# -V1_0.net
KiCad netlist of a schematic drawn in Altium Designer
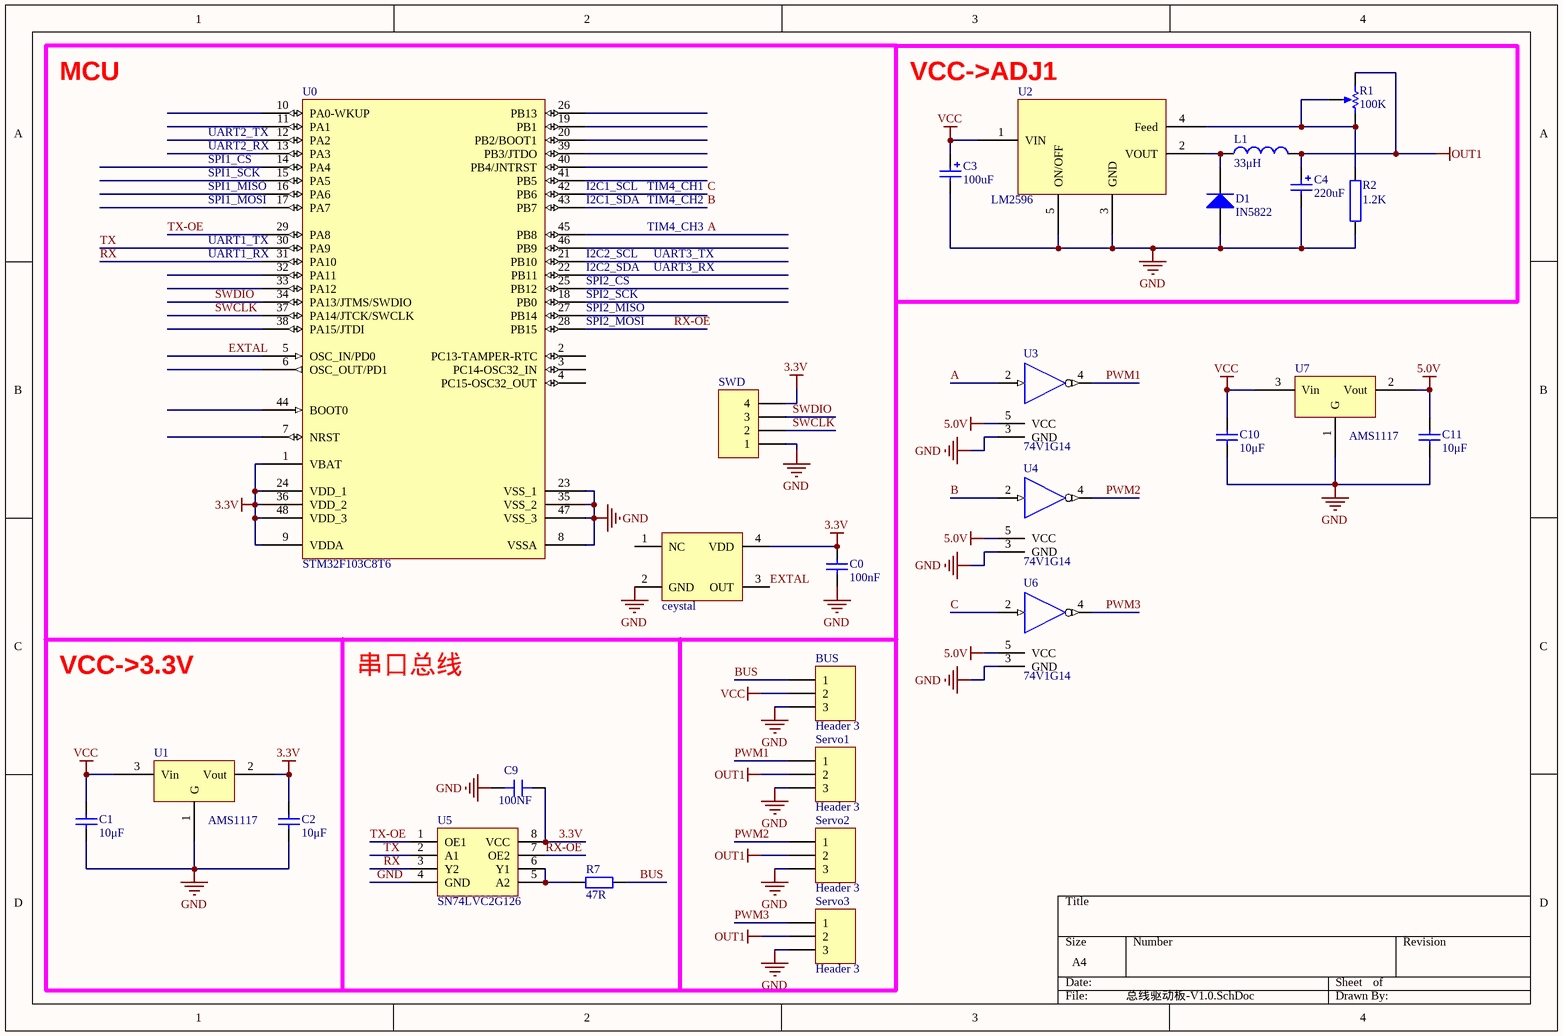
[diagram p0: 总线驱动板-V1.0.SchDoc]

(export (version "E")
  (design (tool "Eeschema 10.0.6"))
  (components
    (comp (ref "BUS")
      (value "Header 3")
      (footprint "3P")
      (description "Header, 3-Pin")
      (fields (field (name "PUBLISHER") "Altium Limited"))
      (libsource (lib "12th_MAINBOARD_3D") (part "Header 3"))
    )
    (comp (ref "C0")
      (value "100nF")
      (footprint "C0603")
      (description "Capacitor (Semiconductor SIM Model)")
      (fields (field (name "Comment") "C0603") (field (name "PUBLISHER") "Altium Limited"))
      (libsource (lib "K66") (part "Cap(0603)"))
    )
    (comp (ref "C1")
      (value "10μF")
      (footprint "Cap_0603")
      (fields (field (name "Comment") "C0603"))
      (libsource (lib "E_Library") (part "Cap0603"))
    )
    (comp (ref "C2")
      (value "10μF")
      (footprint "Cap_0603")
      (fields (field (name "Comment") "C0603"))
      (libsource (lib "E_Library") (part "Cap0603"))
    )
    (comp (ref "C3")
      (value "100uF")
      (footprint "Cap_electrolitic_φ3.5_8")
      (description "Polarized Capacitor (Radial)")
      (fields (field (name "Comment") "CAP_B") (field (name "PUBLISHER") "Altium Limited"))
      (libsource (lib "DR-WiFi Servo") (part "CAP_B"))
    )
    (comp (ref "C4")
      (value "220uF")
      (footprint "Cap_electrolitic_φ3.5_8")
      (description "Polarized Capacitor (Radial)")
      (fields (field (name "Comment") "CAP_B") (field (name "PUBLISHER") "Altium Limited"))
      (libsource (lib "DR-WiFi Servo") (part "CAP_B"))
    )
    (comp (ref "C9")
      (value "100NF")
      (footprint "Cap_0603")
      (fields (field (name "Comment") "C0603"))
      (libsource (lib "常用") (part "Cap 1"))
    )
    (comp (ref "C10")
      (value "10μF")
      (footprint "Cap_0603")
      (fields (field (name "Comment") "C0603"))
      (libsource (lib "E_Library") (part "Cap0603"))
    )
    (comp (ref "C11")
      (value "10μF")
      (footprint "Cap_0603")
      (fields (field (name "Comment") "C0603"))
      (libsource (lib "E_Library") (part "Cap0603"))
    )
    (comp (ref "ceystal")
      (value "32MHz")
      (footprint "crystal")
      (libsource (lib "K66") (part "CRYSTAL OSCILLATOR"))
    )
    (comp (ref "D1") (value "IN5822") (footprint "0805D") (libsource (lib "E_Library") (part "Diode")))
    (comp (ref "L1")
      (value "33μH")
      (footprint "INDUCTOR")
      (fields (field (name "Comment") "INDUCTOR"))
      (libsource (lib "E_Library") (part "INDUCTOR"))
    )
    (comp (ref "R1")
      (value "100K")
      (footprint "SIP-3")
      (description "Potentiometer")
      (fields (field (name "Comment") "RPot") (field (name "PUBLISHER") "Altium Limited"))
      (libsource (lib "Miscellaneous Devices") (part "RPot"))
    )
    (comp (ref "R2")
      (value "1.2K")
      (footprint "Res_0603")
      (description "Resistor")
      (fields (field (name "Comment") "R0603"))
      (libsource (lib "DR-WiFi Servo") (part "RES"))
    )
    (comp (ref "R7")
      (value "47R")
      (footprint "Res_0603")
      (fields (field (name "Comment") "R0603"))
      (libsource (lib "常用") (part "Res2"))
    )
    (comp (ref "Servo1")
      (value "Header 3")
      (footprint "3P")
      (description "Header, 3-Pin")
      (fields (field (name "PUBLISHER") "Altium Limited"))
      (libsource (lib "12th_MAINBOARD_3D") (part "Header 3"))
    )
    (comp (ref "Servo2")
      (value "Header 3")
      (footprint "3P")
      (description "Header, 3-Pin")
      (fields (field (name "PUBLISHER") "Altium Limited"))
      (libsource (lib "12th_MAINBOARD_3D") (part "Header 3"))
    )
    (comp (ref "Servo3")
      (value "Header 3")
      (footprint "3P")
      (description "Header, 3-Pin")
      (fields (field (name "PUBLISHER") "Altium Limited"))
      (libsource (lib "12th_MAINBOARD_3D") (part "Header 3"))
    )
    (comp (ref "SWD")
      (value "Header 4")
      (footprint "HDR1X4_")
      (description "Header, 4-Pin")
      (fields (field (name "PUBLISHER") "Altium Limited"))
      (libsource (lib "Mainboard_for_GraPro_of_Leo_1") (part "Header 4"))
    )
    (comp (ref "U0")
      (value "STM32F103C8T6")
      (footprint "LC-LQFP-48_7x7x05P")
      (description "STM32 ARM-based 32-bit MCU with 64 Kbytes Flash, 48-pin LQFP, Industrial Temperature")
      (fields (field (name "PUBLISHER") "Altium Limited"))
      (libsource (lib "PCB_Project1") (part "STM32F103C8T6"))
    )
    (comp (ref "U1")
      (value "AMS1117")
      (footprint "LC-SOT-89(SOT-89-3)")
      (libsource (lib "my_library") (part "AMS1117"))
    )
    (comp (ref "U2") (value "LM2596") (footprint "LC-TO-263-5") (libsource (lib "电源") (part "LM2596")))
    (comp (ref "U3") (value "74V1G14") (footprint "SOT-23-5") (libsource (lib "E_Library") (part "74V1G14")))
    (comp (ref "U4") (value "74V1G14") (footprint "SOT-23-5") (libsource (lib "E_Library") (part "74V1G14")))
    (comp (ref "U5")
      (value "SN74LVC2G126")
      (footprint "VSSOP-8")
      (libsource (lib "运放逻辑") (part "SN74LVC2G126"))
    )
    (comp (ref "U6") (value "74V1G14") (footprint "SOT-23-5") (libsource (lib "E_Library") (part "74V1G14")))
    (comp (ref "U7")
      (value "AMS1117")
      (footprint "LC-SOT-89(SOT-89-3)")
      (libsource (lib "my_library") (part "AMS1117"))
    )
  )
  (nets
    (net (code "1") (name "/A") (class "Default")
      (node (ref "U0") (pin "45") (pinfunction "PB8_45") (pintype "bidirectional"))
      (node (ref "U3") (pin "2") (pinfunction "A_2") (pintype "input"))
    )
    (net (code "2") (name "/B") (class "Default")
      (node (ref "U0") (pin "43") (pinfunction "PB7_43") (pintype "bidirectional"))
      (node (ref "U4") (pin "2") (pinfunction "A_2") (pintype "input"))
    )
    (net (code "3") (name "/BUS") (class "Default")
      (node (ref "BUS") (pin "1") (pinfunction "1_1") (pintype "passive"))
      (node (ref "R7") (pin "1") (pinfunction "1_1") (pintype "passive"))
    )
    (net (code "4") (name "/C") (class "Default")
      (node (ref "U0") (pin "42") (pinfunction "PB6_42") (pintype "bidirectional"))
      (node (ref "U6") (pin "2") (pinfunction "A_2") (pintype "input"))
    )
    (net (code "5") (name "/EXTAL") (class "Default")
      (node (ref "U0") (pin "5") (pinfunction "OSC_IN/PD0_5") (pintype "input"))
      (node (ref "ceystal") (pin "3") (pinfunction "OUT_3") (pintype "passive"))
    )
    (net (code "6") (name "/PWM1") (class "Default")
      (node (ref "Servo1") (pin "1") (pinfunction "1_1") (pintype "passive"))
      (node (ref "U3") (pin "4") (pinfunction "Y_4") (pintype "output"))
    )
    (net (code "7") (name "/PWM2") (class "Default")
      (node (ref "Servo2") (pin "1") (pinfunction "1_1") (pintype "passive"))
      (node (ref "U4") (pin "4") (pinfunction "Y_4") (pintype "output"))
    )
    (net (code "8") (name "/PWM3") (class "Default")
      (node (ref "Servo3") (pin "1") (pinfunction "1_1") (pintype "passive"))
      (node (ref "U6") (pin "4") (pinfunction "Y_4") (pintype "output"))
    )
    (net (code "9") (name "/RX") (class "Default")
      (node (ref "U0") (pin "31") (pinfunction "PA10_31") (pintype "bidirectional"))
      (node (ref "U5") (pin "3") (pinfunction "Y2_3") (pintype "passive"))
    )
    (net (code "10") (name "/RX-OE") (class "Default")
      (node (ref "U0") (pin "28") (pinfunction "PB15_28") (pintype "bidirectional"))
      (node (ref "U5") (pin "7") (pinfunction "OE2_7") (pintype "passive"))
    )
    (net (code "11") (name "/SWCLK") (class "Default")
      (node (ref "SWD") (pin "2") (pinfunction "2_2") (pintype "passive"))
      (node (ref "U0") (pin "37") (pinfunction "PA14/JTCK/SWCLK_37") (pintype "bidirectional"))
    )
    (net (code "12") (name "/SWDIO") (class "Default")
      (node (ref "SWD") (pin "3") (pinfunction "3_3") (pintype "passive"))
      (node (ref "U0") (pin "34") (pinfunction "PA13/JTMS/SWDIO_34") (pintype "bidirectional"))
    )
    (net (code "13") (name "/TX") (class "Default")
      (node (ref "U0") (pin "30") (pinfunction "PA9_30") (pintype "bidirectional"))
      (node (ref "U5") (pin "2") (pinfunction "A1_2") (pintype "passive"))
    )
    (net (code "14") (name "/TX-OE") (class "Default")
      (node (ref "U0") (pin "29") (pinfunction "PA8_29") (pintype "bidirectional"))
      (node (ref "U5") (pin "1") (pinfunction "OE1_1") (pintype "passive"))
    )
    (net (code "15") (name "3.3V") (class "Default")
      (node (ref "C0") (pin "2") (pinfunction "2_2") (pintype "passive"))
      (node (ref "C2") (pin "2") (pinfunction "2_2") (pintype "passive"))
      (node (ref "C9") (pin "1") (pinfunction "1_1") (pintype "passive"))
      (node (ref "SWD") (pin "4") (pinfunction "4_4") (pintype "passive"))
      (node (ref "U0") (pin "1") (pinfunction "VBAT_1") (pintype "power_in"))
      (node (ref "U0") (pin "24") (pinfunction "VDD_1_24") (pintype "power_in"))
      (node (ref "U0") (pin "36") (pinfunction "VDD_2_36") (pintype "power_in"))
      (node (ref "U0") (pin "48") (pinfunction "VDD_3_48") (pintype "power_in"))
      (node (ref "U0") (pin "9") (pinfunction "VDDA_9") (pintype "power_in"))
      (node (ref "U1") (pin "2") (pinfunction "Vout_2") (pintype "passive"))
      (node (ref "U5") (pin "8") (pinfunction "VCC_8") (pintype "passive"))
      (node (ref "ceystal") (pin "4") (pinfunction "VDD_4") (pintype "passive"))
    )
    (net (code "16") (name "5.0V") (class "Default")
      (node (ref "C11") (pin "2") (pinfunction "2_2") (pintype "passive"))
      (node (ref "U3") (pin "5") (pinfunction "VCC_5") (pintype "power_in"))
      (node (ref "U4") (pin "5") (pinfunction "VCC_5") (pintype "power_in"))
      (node (ref "U6") (pin "5") (pinfunction "VCC_5") (pintype "power_in"))
      (node (ref "U7") (pin "2") (pinfunction "Vout_2") (pintype "passive"))
    )
    (net (code "17") (name "GND") (class "Default")
      (node (ref "BUS") (pin "3") (pinfunction "3_3") (pintype "passive"))
      (node (ref "C0") (pin "1") (pinfunction "1_1") (pintype "passive"))
      (node (ref "C1") (pin "1") (pinfunction "1_1") (pintype "passive"))
      (node (ref "C10") (pin "1") (pinfunction "1_1") (pintype "passive"))
      (node (ref "C11") (pin "1") (pinfunction "1_1") (pintype "passive"))
      (node (ref "C2") (pin "1") (pinfunction "1_1") (pintype "passive"))
      (node (ref "C3") (pin "2") (pinfunction "2_2") (pintype "passive"))
      (node (ref "C4") (pin "2") (pinfunction "2_2") (pintype "passive"))
      (node (ref "C9") (pin "2") (pinfunction "2_2") (pintype "passive"))
      (node (ref "D1") (pin "A") (pinfunction "A_A") (pintype "passive"))
      (node (ref "R2") (pin "2") (pinfunction "BOT_2") (pintype "passive"))
      (node (ref "SWD") (pin "1") (pinfunction "1_1") (pintype "passive"))
      (node (ref "Servo1") (pin "3") (pinfunction "3_3") (pintype "passive"))
      (node (ref "Servo2") (pin "3") (pinfunction "3_3") (pintype "passive"))
      (node (ref "Servo3") (pin "3") (pinfunction "3_3") (pintype "passive"))
      (node (ref "U0") (pin "23") (pinfunction "VSS_1_23") (pintype "power_in"))
      (node (ref "U0") (pin "35") (pinfunction "VSS_2_35") (pintype "power_in"))
      (node (ref "U0") (pin "47") (pinfunction "VSS_3_47") (pintype "power_in"))
      (node (ref "U0") (pin "8") (pinfunction "VSSA_8") (pintype "power_in"))
      (node (ref "U1") (pin "1") (pinfunction "G_1") (pintype "passive"))
      (node (ref "U2") (pin "3") (pinfunction "GND_3") (pintype "passive"))
      (node (ref "U2") (pin "5") (pinfunction "ON/OFF_5") (pintype "passive"))
      (node (ref "U3") (pin "3") (pinfunction "GND_3") (pintype "power_in"))
      (node (ref "U4") (pin "3") (pinfunction "GND_3") (pintype "power_in"))
      (node (ref "U5") (pin "4") (pinfunction "GND_4") (pintype "passive"))
      (node (ref "U6") (pin "3") (pinfunction "GND_3") (pintype "power_in"))
      (node (ref "U7") (pin "1") (pinfunction "G_1") (pintype "passive"))
      (node (ref "ceystal") (pin "2") (pinfunction "GND_2") (pintype "passive"))
    )
    (net (code "18") (name "Net-(R1-BOT)") (class "Default")
      (node (ref "R1") (pin "2") (pinfunction "BOT_2") (pintype "passive"))
      (node (ref "R1") (pin "3") (pinfunction "TAP_3") (pintype "passive"))
      (node (ref "R2") (pin "1") (pinfunction "TOP_1") (pintype "passive"))
      (node (ref "U2") (pin "4") (pinfunction "Feed_4") (pintype "passive"))
    )
    (net (code "19") (name "Net-(U2-VOUT)") (class "Default")
      (node (ref "D1") (pin "K") (pinfunction "K_K") (pintype "passive"))
      (node (ref "L1") (pin "1") (pinfunction "1_1") (pintype "passive"))
      (node (ref "U2") (pin "2") (pinfunction "VOUT_2") (pintype "passive"))
    )
    (net (code "20") (name "Net-(U5-A2)") (class "Default")
      (node (ref "R7") (pin "2") (pinfunction "2_2") (pintype "passive"))
      (node (ref "U5") (pin "5") (pinfunction "A2_5") (pintype "passive"))
      (node (ref "U5") (pin "6") (pinfunction "Y1_6") (pintype "passive"))
    )
    (net (code "21") (name "OUT1") (class "Default")
      (node (ref "C4") (pin "1") (pinfunction "1_1") (pintype "passive"))
      (node (ref "L1") (pin "2") (pinfunction "2_2") (pintype "passive"))
      (node (ref "R1") (pin "1") (pinfunction "TOP_1") (pintype "passive"))
      (node (ref "Servo1") (pin "2") (pinfunction "2_2") (pintype "passive"))
      (node (ref "Servo2") (pin "2") (pinfunction "2_2") (pintype "passive"))
      (node (ref "Servo3") (pin "2") (pinfunction "2_2") (pintype "passive"))
    )
    (net (code "22") (name "VCC") (class "Default")
      (node (ref "BUS") (pin "2") (pinfunction "2_2") (pintype "passive"))
      (node (ref "C1") (pin "2") (pinfunction "2_2") (pintype "passive"))
      (node (ref "C10") (pin "2") (pinfunction "2_2") (pintype "passive"))
      (node (ref "C3") (pin "1") (pinfunction "1_1") (pintype "passive"))
      (node (ref "U1") (pin "3") (pinfunction "Vin_3") (pintype "passive"))
      (node (ref "U2") (pin "1") (pinfunction "VIN_1") (pintype "passive"))
      (node (ref "U7") (pin "3") (pinfunction "Vin_3") (pintype "passive"))
    )
    (net (code "23") (name "unconnected-(U0-BOOT0-Pad44)") (class "Default")
      (node (ref "U0") (pin "44") (pinfunction "BOOT0_44") (pintype "input"))
    )
    (net (code "24") (name "unconnected-(U0-NRST-Pad7)") (class "Default")
      (node (ref "U0") (pin "7") (pinfunction "NRST_7") (pintype "bidirectional"))
    )
    (net (code "25") (name "unconnected-(U0-OSC_OUT{slash}PD1-Pad6)") (class "Default")
      (node (ref "U0") (pin "6") (pinfunction "OSC_OUT/PD1_6") (pintype "output"))
    )
    (net (code "26") (name "unconnected-(U0-PA0-WKUP-Pad10)") (class "Default")
      (node (ref "U0") (pin "10") (pinfunction "PA0-WKUP_10") (pintype "bidirectional"))
    )
    (net (code "27") (name "unconnected-(U0-PA1-Pad11)") (class "Default")
      (node (ref "U0") (pin "11") (pinfunction "PA1_11") (pintype "bidirectional"))
    )
    (net (code "28") (name "unconnected-(U0-PA2-Pad12)") (class "Default")
      (node (ref "U0") (pin "12") (pinfunction "PA2_12") (pintype "bidirectional"))
    )
    (net (code "29") (name "unconnected-(U0-PA3-Pad13)") (class "Default")
      (node (ref "U0") (pin "13") (pinfunction "PA3_13") (pintype "bidirectional"))
    )
    (net (code "30") (name "unconnected-(U0-PA4-Pad14)") (class "Default")
      (node (ref "U0") (pin "14") (pinfunction "PA4_14") (pintype "bidirectional"))
    )
    (net (code "31") (name "unconnected-(U0-PA5-Pad15)") (class "Default")
      (node (ref "U0") (pin "15") (pinfunction "PA5_15") (pintype "bidirectional"))
    )
    (net (code "32") (name "unconnected-(U0-PA6-Pad16)") (class "Default")
      (node (ref "U0") (pin "16") (pinfunction "PA6_16") (pintype "bidirectional"))
    )
    (net (code "33") (name "unconnected-(U0-PA7-Pad17)") (class "Default")
      (node (ref "U0") (pin "17") (pinfunction "PA7_17") (pintype "bidirectional"))
    )
    (net (code "34") (name "unconnected-(U0-PA11-Pad32)") (class "Default")
      (node (ref "U0") (pin "32") (pinfunction "PA11_32") (pintype "bidirectional"))
    )
    (net (code "35") (name "unconnected-(U0-PA12-Pad33)") (class "Default")
      (node (ref "U0") (pin "33") (pinfunction "PA12_33") (pintype "bidirectional"))
    )
    (net (code "36") (name "unconnected-(U0-PA15{slash}JTDI-Pad38)") (class "Default")
      (node (ref "U0") (pin "38") (pinfunction "PA15/JTDI_38") (pintype "bidirectional"))
    )
    (net (code "37") (name "unconnected-(U0-PB0-Pad18)") (class "Default")
      (node (ref "U0") (pin "18") (pinfunction "PB0_18") (pintype "bidirectional"))
    )
    (net (code "38") (name "unconnected-(U0-PB1-Pad19)") (class "Default")
      (node (ref "U0") (pin "19") (pinfunction "PB1_19") (pintype "bidirectional"))
    )
    (net (code "39") (name "unconnected-(U0-PB2{slash}BOOT1-Pad20)") (class "Default")
      (node (ref "U0") (pin "20") (pinfunction "PB2/BOOT1_20") (pintype "bidirectional"))
    )
    (net (code "40") (name "unconnected-(U0-PB3{slash}JTDO-Pad39)") (class "Default")
      (node (ref "U0") (pin "39") (pinfunction "PB3/JTDO_39") (pintype "bidirectional"))
    )
    (net (code "41") (name "unconnected-(U0-PB4{slash}JNTRST-Pad40)") (class "Default")
      (node (ref "U0") (pin "40") (pinfunction "PB4/JNTRST_40") (pintype "bidirectional"))
    )
    (net (code "42") (name "unconnected-(U0-PB5-Pad41)") (class "Default")
      (node (ref "U0") (pin "41") (pinfunction "PB5_41") (pintype "bidirectional"))
    )
    (net (code "43") (name "unconnected-(U0-PB9-Pad46)") (class "Default")
      (node (ref "U0") (pin "46") (pinfunction "PB9_46") (pintype "bidirectional"))
    )
    (net (code "44") (name "unconnected-(U0-PB10-Pad21)") (class "Default")
      (node (ref "U0") (pin "21") (pinfunction "PB10_21") (pintype "bidirectional"))
    )
    (net (code "45") (name "unconnected-(U0-PB11-Pad22)") (class "Default")
      (node (ref "U0") (pin "22") (pinfunction "PB11_22") (pintype "bidirectional"))
    )
    (net (code "46") (name "unconnected-(U0-PB12-Pad25)") (class "Default")
      (node (ref "U0") (pin "25") (pinfunction "PB12_25") (pintype "bidirectional"))
    )
    (net (code "47") (name "unconnected-(U0-PB13-Pad26)") (class "Default")
      (node (ref "U0") (pin "26") (pinfunction "PB13_26") (pintype "bidirectional"))
    )
    (net (code "48") (name "unconnected-(U0-PB14-Pad27)") (class "Default")
      (node (ref "U0") (pin "27") (pinfunction "PB14_27") (pintype "bidirectional"))
    )
    (net (code "49") (name "unconnected-(U0-PC13-TAMPER-RTC-Pad2)") (class "Default")
      (node (ref "U0") (pin "2") (pinfunction "PC13-TAMPER-RTC_2") (pintype "bidirectional"))
    )
    (net (code "50") (name "unconnected-(U0-PC14-OSC32_IN-Pad3)") (class "Default")
      (node (ref "U0") (pin "3") (pinfunction "PC14-OSC32_IN_3") (pintype "bidirectional"))
    )
    (net (code "51") (name "unconnected-(U0-PC15-OSC32_OUT-Pad4)") (class "Default")
      (node (ref "U0") (pin "4") (pinfunction "PC15-OSC32_OUT_4") (pintype "bidirectional"))
    )
    (net (code "52") (name "unconnected-(ceystal-NC-Pad1)") (class "Default")
      (node (ref "ceystal") (pin "1") (pinfunction "NC_1") (pintype "passive"))
    )
  )
)
